# InvidualShelfSR.net
KiCad netlist of a schematic drawn in Altium Designer
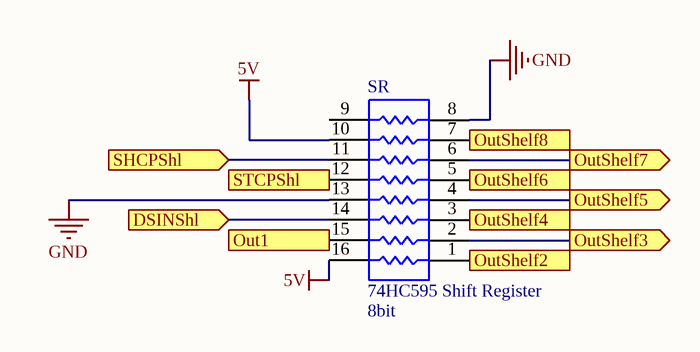
[diagram p0: InvidualShelfSR.SchDoc]

(export (version "E")
  (design (tool "Eeschema 10.0.6"))
  (components
    (comp (ref "SR")
      (value "74HC595 Shift Register")
      (footprint "SO-16_L")
      (description "Isolated Resistor Network")
      (fields (field (name "ALTIUM_VALUE") "8bit") (field (name "PUBLISHER") "Altium Limited"))
      (libsource (lib "Miscellaneous Devices") (part "Res Pack3"))
    )
  )
  (nets
    (net (code "1") (name "/DSINShl") (class "Default")
      (node (ref "SR") (pin "14") (pinfunction "14_14") (pintype "passive"))
    )
    (net (code "2") (name "/Out1") (class "Default")
      (node (ref "SR") (pin "15") (pinfunction "15_15") (pintype "passive"))
    )
    (net (code "3") (name "/OutShelf2") (class "Default")
      (node (ref "SR") (pin "1") (pinfunction "1_1") (pintype "passive"))
    )
    (net (code "4") (name "/OutShelf3") (class "Default")
      (node (ref "SR") (pin "2") (pinfunction "2_2") (pintype "passive"))
    )
    (net (code "5") (name "/OutShelf4") (class "Default")
      (node (ref "SR") (pin "3") (pinfunction "3_3") (pintype "passive"))
    )
    (net (code "6") (name "/OutShelf5") (class "Default")
      (node (ref "SR") (pin "4") (pinfunction "4_4") (pintype "passive"))
    )
    (net (code "7") (name "/OutShelf6") (class "Default")
      (node (ref "SR") (pin "5") (pinfunction "5_5") (pintype "passive"))
    )
    (net (code "8") (name "/OutShelf7") (class "Default")
      (node (ref "SR") (pin "6") (pinfunction "6_6") (pintype "passive"))
    )
    (net (code "9") (name "/OutShelf8") (class "Default")
      (node (ref "SR") (pin "7") (pinfunction "7_7") (pintype "passive"))
    )
    (net (code "10") (name "/SHCPShl") (class "Default")
      (node (ref "SR") (pin "11") (pinfunction "11_11") (pintype "passive"))
    )
    (net (code "11") (name "/STCPShl") (class "Default")
      (node (ref "SR") (pin "12") (pinfunction "12_12") (pintype "passive"))
    )
    (net (code "12") (name "5V") (class "Default")
      (node (ref "SR") (pin "10") (pinfunction "10_10") (pintype "passive"))
      (node (ref "SR") (pin "16") (pinfunction "16_16") (pintype "passive"))
    )
    (net (code "13") (name "GND") (class "Default")
      (node (ref "SR") (pin "13") (pinfunction "13_13") (pintype "passive"))
      (node (ref "SR") (pin "8") (pinfunction "8_8") (pintype "passive"))
    )
    (net (code "14") (name "unconnected-(SR-Pad9)") (class "Default")
      (node (ref "SR") (pin "9") (pinfunction "9_9") (pintype "passive"))
    )
  )
)
